# SCH_d_02_e_03.net
KiCad netlist of a schematic drawn in EasyEDA
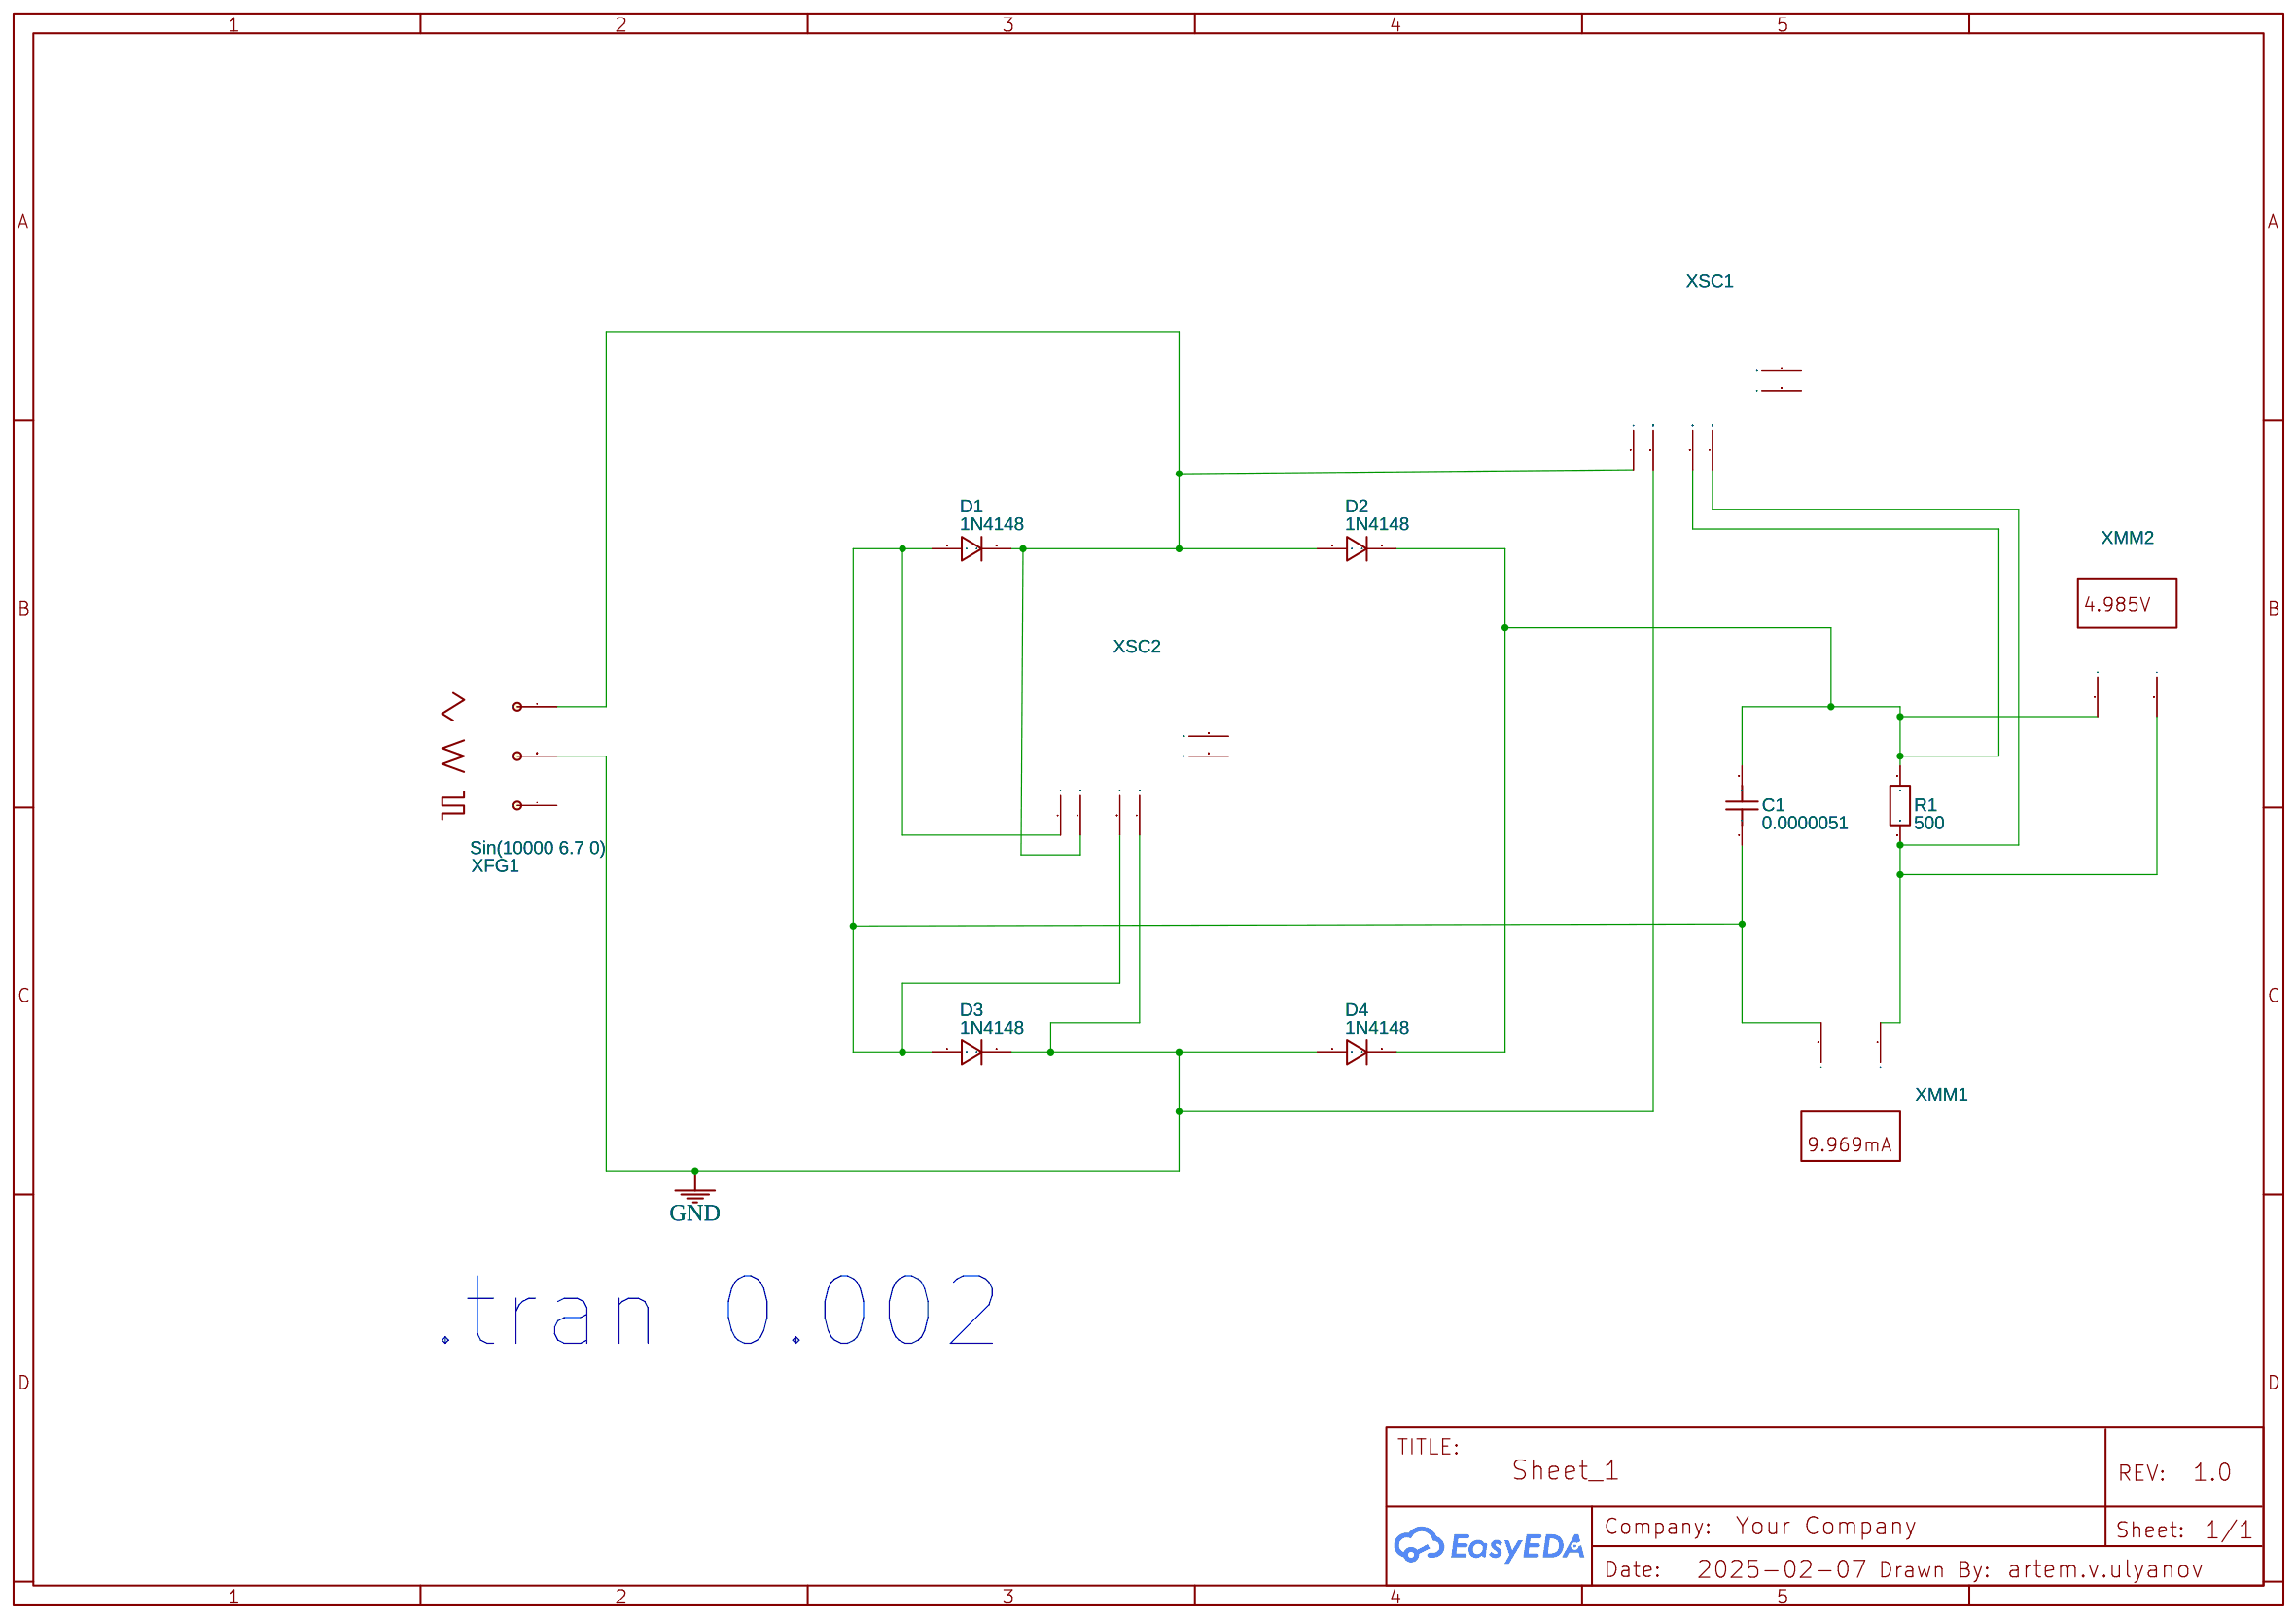
[diagram p0: schematic sheet]

(export (version "E")
  (design (tool "Eeschema 10.0.6"))
  (components
    (comp (ref "C1") (value "0.0000051") (libsource (lib "") (part "Capacitor_US")))
    (comp (ref "D1") (value "1N4148") (libsource (lib "") (part "1N4148")))
    (comp (ref "D2") (value "1N4148") (libsource (lib "") (part "1N4148")))
    (comp (ref "D3") (value "1N4148") (libsource (lib "") (part "1N4148")))
    (comp (ref "D4") (value "1N4148") (libsource (lib "") (part "1N4148")))
    (comp (ref "R1") (value "500") (libsource (lib "") (part "R_0603_EU")))
    (comp (ref "XFG1") (value "Sin(10000 6.7 0)") (libsource (lib "") (part "FUNCTIONGENERATOR")))
    (comp (ref "XMM1") (value "Multimeter") (libsource (lib "") (part "MULTIMETER")))
    (comp (ref "XMM2") (value "Multimeter") (libsource (lib "") (part "MULTIMETER_1")))
    (comp (ref "XSC1") (value "Oscilloscope") (libsource (lib "") (part "OSCILLOSCOPE")))
    (comp (ref "XSC2") (value "Oscilloscope") (libsource (lib "") (part "OSCILLOSCOPE")))
  )
  (nets
    (net (code "1") (name "GND") (class "Default")
      (node (ref "D3") (pin "2") (pinfunction "K_2") (pintype "unspecified"))
      (node (ref "D4") (pin "1") (pinfunction "A_1") (pintype "unspecified"))
      (node (ref "XFG1") (pin "COM") (pinfunction "COM_COM") (pintype "unspecified"))
      (node (ref "XSC1") (pin "2") (pinfunction "GND1_2") (pintype "unspecified"))
      (node (ref "XSC2") (pin "4") (pinfunction "GND2_4") (pintype "unspecified"))
    )
    (net (code "2") (name "Net-(D1-A)") (class "Default")
      (node (ref "C1") (pin "1") (pinfunction "1_1") (pintype "unspecified"))
      (node (ref "D1") (pin "1") (pinfunction "A_1") (pintype "unspecified"))
      (node (ref "D3") (pin "1") (pinfunction "A_1") (pintype "unspecified"))
      (node (ref "XMM1") (pin "2") (pinfunction "I_2") (pintype "unspecified"))
      (node (ref "XSC2") (pin "1") (pinfunction "A_1") (pintype "unspecified"))
      (node (ref "XSC2") (pin "3") (pinfunction "B_3") (pintype "unspecified"))
    )
    (net (code "3") (name "Net-(D1-K)") (class "Default")
      (node (ref "D1") (pin "2") (pinfunction "K_2") (pintype "unspecified"))
      (node (ref "D2") (pin "1") (pinfunction "A_1") (pintype "unspecified"))
      (node (ref "XFG1") (pin "+") (pinfunction "+_+") (pintype "unspecified"))
      (node (ref "XSC1") (pin "1") (pinfunction "A_1") (pintype "unspecified"))
      (node (ref "XSC2") (pin "2") (pinfunction "GND1_2") (pintype "unspecified"))
    )
    (net (code "4") (name "Net-(D2-K)") (class "Default")
      (node (ref "C1") (pin "2") (pinfunction "2_2") (pintype "unspecified"))
      (node (ref "D2") (pin "2") (pinfunction "K_2") (pintype "unspecified"))
      (node (ref "D4") (pin "2") (pinfunction "K_2") (pintype "unspecified"))
      (node (ref "R1") (pin "1") (pinfunction "1_1") (pintype "unspecified"))
      (node (ref "XMM2") (pin "1") (pinfunction "+_1") (pintype "unspecified"))
      (node (ref "XSC1") (pin "3") (pinfunction "B_3") (pintype "unspecified"))
    )
    (net (code "5") (name "Net-(XMM1-+)") (class "Default")
      (node (ref "R1") (pin "2") (pinfunction "2_2") (pintype "unspecified"))
      (node (ref "XMM1") (pin "1") (pinfunction "+_1") (pintype "unspecified"))
      (node (ref "XMM2") (pin "2") (pinfunction "I_2") (pintype "unspecified"))
      (node (ref "XSC1") (pin "4") (pinfunction "GND2_4") (pintype "unspecified"))
    )
    (net (code "6") (name "unconnected-(XFG1-Pad-)") (class "Default")
      (node (ref "XFG1") (pin "-") (pinfunction "-_-") (pintype "unspecified"))
    )
    (net (code "7") (name "unconnected-(XSC1-T+-Pad5)") (class "Default")
      (node (ref "XSC1") (pin "5") (pinfunction "T+_5") (pintype "unspecified"))
    )
    (net (code "8") (name "unconnected-(XSC1-T--Pad6)") (class "Default")
      (node (ref "XSC1") (pin "6") (pinfunction "T-_6") (pintype "unspecified"))
    )
    (net (code "9") (name "unconnected-(XSC2-T+-Pad5)") (class "Default")
      (node (ref "XSC2") (pin "5") (pinfunction "T+_5") (pintype "unspecified"))
    )
    (net (code "10") (name "unconnected-(XSC2-T--Pad6)") (class "Default")
      (node (ref "XSC2") (pin "6") (pinfunction "T-_6") (pintype "unspecified"))
    )
  )
)
